# Ariel_v3.net
KiCad netlist of a schematic drawn in EAGLE
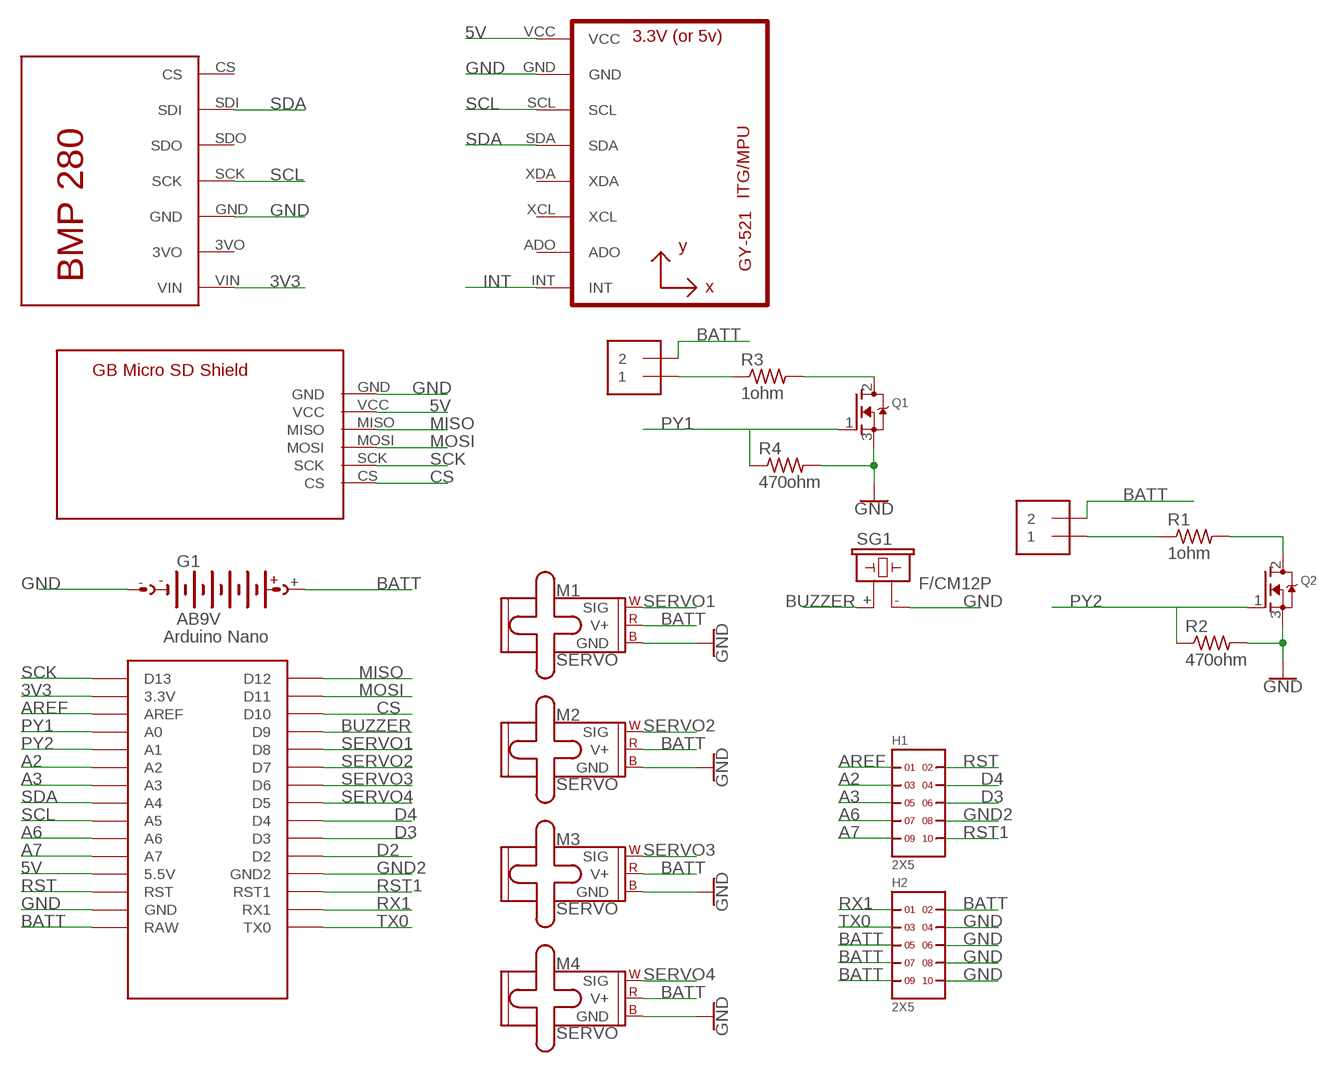
[diagram p0: schematic, sheet 1]

(export (version "E")
  (design (tool "Eeschema 10.0.6"))
  (components
    (comp (ref "G1")
      (value "AB9V")
      (footprint "eagle-import:AB9V")
      (libsource (lib "eagle-import") (part "AB9V"))
    )
    (comp (ref "H1")
      (value "2X5")
      (footprint "eagle-import:2X5")
      (libsource (lib "eagle-import") (part "2X5"))
    )
    (comp (ref "H2")
      (value "2X5")
      (footprint "eagle-import:2X5")
      (libsource (lib "eagle-import") (part "2X5"))
    )
    (comp (ref "J1")
      (value "1X2-3.5MM")
      (footprint "eagle-import:1X2-3.5MM")
      (libsource (lib "eagle-import") (part "1X2-3.5MM"))
    )
    (comp (ref "J2")
      (value "1X2-3.5MM")
      (footprint "eagle-import:1X2-3.5MM")
      (libsource (lib "eagle-import") (part "1X2-3.5MM"))
    )
    (comp (ref "M1")
      (value "SERVO")
      (footprint "eagle-import:1X03")
      (libsource (lib "eagle-import") (part "SERVO"))
    )
    (comp (ref "M2")
      (value "SERVO")
      (footprint "eagle-import:1X03")
      (libsource (lib "eagle-import") (part "SERVO"))
    )
    (comp (ref "M3")
      (value "SERVO")
      (footprint "eagle-import:1X03")
      (libsource (lib "eagle-import") (part "SERVO"))
    )
    (comp (ref "M4")
      (value "SERVO")
      (footprint "eagle-import:1X03")
      (libsource (lib "eagle-import") (part "SERVO"))
    )
    (comp (ref "Q1")
      (value "MOSFET-NGDS_TO220V")
      (footprint "eagle-import:TO220V")
      (libsource (lib "eagle-import") (part "MOSFET-NGDS_TO220V"))
    )
    (comp (ref "Q2")
      (value "MOSFET-NGDS_TO220V")
      (footprint "eagle-import:TO220V")
      (libsource (lib "eagle-import") (part "MOSFET-NGDS_TO220V"))
    )
    (comp (ref "R1")
      (value "1ohm")
      (footprint "eagle-import:0805-THM")
      (libsource (lib "eagle-import") (part "FLIPFLOP-RES"))
    )
    (comp (ref "R2")
      (value "470ohm")
      (footprint "eagle-import:0805-THM")
      (libsource (lib "eagle-import") (part "FLIPFLOP-RES"))
    )
    (comp (ref "R3")
      (value "1ohm")
      (footprint "eagle-import:0805-THM")
      (libsource (lib "eagle-import") (part "FLIPFLOP-RES"))
    )
    (comp (ref "R4")
      (value "470ohm")
      (footprint "eagle-import:0805-THM")
      (libsource (lib "eagle-import") (part "FLIPFLOP-RES"))
    )
    (comp (ref "SG1")
      (value "F/CM12P")
      (footprint "eagle-import:F_CM12P")
      (libsource (lib "eagle-import") (part "F/CM12P"))
    )
    (comp (ref "U$1")
      (value "NANO")
      (footprint "eagle-import:NANO")
      (libsource (lib "eagle-import") (part "NANO"))
    )
    (comp (ref "U$2")
      (value "BMP280")
      (footprint "eagle-import:BMP280")
      (libsource (lib "eagle-import") (part "BMP280"))
    )
    (comp (ref "U$3")
      (value "GBMICROSDSHIELD")
      (footprint "eagle-import:GBMICROSDSHIELD")
      (libsource (lib "eagle-import") (part "GBMICROSDSHIELD"))
    )
    (comp (ref "U1")
      (value "GY-521MPU6050")
      (footprint "eagle-import:GY-521")
      (libsource (lib "eagle-import") (part "GY-521MPU6050"))
    )
  )
  (nets
    (net (code "1") (name "/3V3") (class "Default")
      (node (ref "U$1") (pin "3.3V") (pinfunction "3.3V_3.3V") (pintype "bidirectional"))
      (node (ref "U$2") (pin "VIN") (pinfunction "VIN_VIN") (pintype "bidirectional"))
    )
    (net (code "2") (name "/5V") (class "Default")
      (node (ref "U$1") (pin "5V") (pinfunction "5.5V_5V") (pintype "bidirectional"))
      (node (ref "U$3") (pin "VCC") (pinfunction "VCC_VCC") (pintype "bidirectional"))
      (node (ref "U1") (pin "VCC") (pinfunction "VCC_VCC") (pintype "bidirectional"))
    )
    (net (code "3") (name "/A2") (class "Default")
      (node (ref "H1") (pin "3") (pinfunction "3_3") (pintype "bidirectional"))
      (node (ref "U$1") (pin "A2") (pinfunction "A2_A2") (pintype "bidirectional"))
    )
    (net (code "4") (name "/A3") (class "Default")
      (node (ref "H1") (pin "5") (pinfunction "5_5") (pintype "bidirectional"))
      (node (ref "U$1") (pin "A3") (pinfunction "A3_A3") (pintype "bidirectional"))
    )
    (net (code "5") (name "/A6") (class "Default")
      (node (ref "H1") (pin "7") (pinfunction "7_7") (pintype "bidirectional"))
      (node (ref "U$1") (pin "A6") (pinfunction "A6_A6") (pintype "bidirectional"))
    )
    (net (code "6") (name "/A7") (class "Default")
      (node (ref "H1") (pin "9") (pinfunction "9_9") (pintype "bidirectional"))
      (node (ref "U$1") (pin "A7") (pinfunction "A7_A7") (pintype "bidirectional"))
    )
    (net (code "7") (name "/AREF") (class "Default")
      (node (ref "H1") (pin "1") (pinfunction "1_1") (pintype "bidirectional"))
      (node (ref "U$1") (pin "AREF") (pinfunction "AREF_AREF") (pintype "bidirectional"))
    )
    (net (code "8") (name "/BATT") (class "Default")
      (node (ref "G1") (pin "+") (pinfunction "+_+") (pintype "passive"))
      (node (ref "H2") (pin "2") (pinfunction "2_2") (pintype "bidirectional"))
      (node (ref "H2") (pin "5") (pinfunction "5_5") (pintype "bidirectional"))
      (node (ref "H2") (pin "7") (pinfunction "7_7") (pintype "bidirectional"))
      (node (ref "H2") (pin "9") (pinfunction "9_9") (pintype "bidirectional"))
      (node (ref "J1") (pin "2") (pinfunction "2_2") (pintype "passive"))
      (node (ref "J2") (pin "2") (pinfunction "2_2") (pintype "passive"))
      (node (ref "M1") (pin "2") (pinfunction "V+_2") (pintype "bidirectional"))
      (node (ref "M2") (pin "2") (pinfunction "V+_2") (pintype "bidirectional"))
      (node (ref "M3") (pin "2") (pinfunction "V+_2") (pintype "bidirectional"))
      (node (ref "M4") (pin "2") (pinfunction "V+_2") (pintype "bidirectional"))
      (node (ref "U$1") (pin "RAW") (pinfunction "RAW_RAW") (pintype "bidirectional"))
    )
    (net (code "9") (name "/BUZZER") (class "Default")
      (node (ref "SG1") (pin "+") (pinfunction "1_+") (pintype "passive"))
      (node (ref "U$1") (pin "D9") (pinfunction "D9_D9") (pintype "bidirectional"))
    )
    (net (code "10") (name "/CS") (class "Default")
      (node (ref "U$1") (pin "D10") (pinfunction "D10_D10") (pintype "bidirectional"))
      (node (ref "U$3") (pin "CS") (pinfunction "CS_CS") (pintype "bidirectional"))
    )
    (net (code "11") (name "/D2") (class "Default")
      (node (ref "U$1") (pin "D2") (pinfunction "D2_D2") (pintype "bidirectional"))
    )
    (net (code "12") (name "/D3") (class "Default")
      (node (ref "H1") (pin "6") (pinfunction "6_6") (pintype "bidirectional"))
      (node (ref "U$1") (pin "D3") (pinfunction "D3_D3") (pintype "bidirectional"))
    )
    (net (code "13") (name "/D4") (class "Default")
      (node (ref "H1") (pin "4") (pinfunction "4_4") (pintype "bidirectional"))
      (node (ref "U$1") (pin "D4") (pinfunction "D4_D4") (pintype "bidirectional"))
    )
    (net (code "14") (name "/GND2") (class "Default")
      (node (ref "H1") (pin "8") (pinfunction "8_8") (pintype "bidirectional"))
      (node (ref "U$1") (pin "GND1") (pinfunction "GND2_GND1") (pintype "bidirectional"))
    )
    (net (code "15") (name "/INT") (class "Default")
      (node (ref "U1") (pin "INT") (pinfunction "INT_INT") (pintype "bidirectional"))
    )
    (net (code "16") (name "/MISO") (class "Default")
      (node (ref "U$1") (pin "D12") (pinfunction "D12_D12") (pintype "bidirectional"))
      (node (ref "U$3") (pin "MISO") (pinfunction "MISO_MISO") (pintype "bidirectional"))
    )
    (net (code "17") (name "/MOSI") (class "Default")
      (node (ref "U$1") (pin "D11") (pinfunction "D11_D11") (pintype "bidirectional"))
      (node (ref "U$3") (pin "MOSI") (pinfunction "MOSI_MOSI") (pintype "bidirectional"))
    )
    (net (code "18") (name "/PY1") (class "Default")
      (node (ref "Q1") (pin "1") (pinfunction "G_1") (pintype "bidirectional"))
      (node (ref "R4") (pin "1") (pinfunction "1_1") (pintype "passive"))
      (node (ref "U$1") (pin "A0") (pinfunction "A0_A0") (pintype "bidirectional"))
    )
    (net (code "19") (name "/PY2") (class "Default")
      (node (ref "Q2") (pin "1") (pinfunction "G_1") (pintype "bidirectional"))
      (node (ref "R2") (pin "1") (pinfunction "1_1") (pintype "passive"))
      (node (ref "U$1") (pin "A1") (pinfunction "A1_A1") (pintype "bidirectional"))
    )
    (net (code "20") (name "/RST") (class "Default")
      (node (ref "H1") (pin "2") (pinfunction "2_2") (pintype "bidirectional"))
      (node (ref "U$1") (pin "RST") (pinfunction "RST_RST") (pintype "bidirectional"))
    )
    (net (code "21") (name "/RST1") (class "Default")
      (node (ref "H1") (pin "10") (pinfunction "10_10") (pintype "bidirectional"))
      (node (ref "U$1") (pin "RST1") (pinfunction "RST1_RST1") (pintype "bidirectional"))
    )
    (net (code "22") (name "/RX1") (class "Default")
      (node (ref "H2") (pin "1") (pinfunction "1_1") (pintype "bidirectional"))
      (node (ref "U$1") (pin "RX1") (pinfunction "RX1_RX1") (pintype "bidirectional"))
    )
    (net (code "23") (name "/SCK") (class "Default")
      (node (ref "U$1") (pin "D13") (pinfunction "D13_D13") (pintype "bidirectional"))
      (node (ref "U$3") (pin "SCK") (pinfunction "SCK_SCK") (pintype "bidirectional"))
    )
    (net (code "24") (name "/SCL") (class "Default")
      (node (ref "U$1") (pin "A5") (pinfunction "A5_A5") (pintype "bidirectional"))
      (node (ref "U$2") (pin "SCK") (pinfunction "SCK_SCK") (pintype "bidirectional"))
      (node (ref "U1") (pin "SCL") (pinfunction "SCL_SCL") (pintype "bidirectional"))
    )
    (net (code "25") (name "/SDA") (class "Default")
      (node (ref "U$1") (pin "A4") (pinfunction "A4_A4") (pintype "bidirectional"))
      (node (ref "U$2") (pin "SDI") (pinfunction "SDI_SDI") (pintype "bidirectional"))
      (node (ref "U1") (pin "SDA") (pinfunction "SDA_SDA") (pintype "bidirectional"))
    )
    (net (code "26") (name "/SERVO1") (class "Default")
      (node (ref "M1") (pin "1") (pinfunction "SIG_1") (pintype "bidirectional"))
      (node (ref "U$1") (pin "D8") (pinfunction "D8_D8") (pintype "bidirectional"))
    )
    (net (code "27") (name "/SERVO2") (class "Default")
      (node (ref "M2") (pin "1") (pinfunction "SIG_1") (pintype "bidirectional"))
      (node (ref "U$1") (pin "D7") (pinfunction "D7_D7") (pintype "bidirectional"))
    )
    (net (code "28") (name "/SERVO3") (class "Default")
      (node (ref "M3") (pin "1") (pinfunction "SIG_1") (pintype "bidirectional"))
      (node (ref "U$1") (pin "D6") (pinfunction "D6_D6") (pintype "bidirectional"))
    )
    (net (code "29") (name "/SERVO4") (class "Default")
      (node (ref "M4") (pin "1") (pinfunction "SIG_1") (pintype "bidirectional"))
      (node (ref "U$1") (pin "D5") (pinfunction "D5_D5") (pintype "bidirectional"))
    )
    (net (code "30") (name "/TX0") (class "Default")
      (node (ref "H2") (pin "3") (pinfunction "3_3") (pintype "bidirectional"))
      (node (ref "U$1") (pin "TX0") (pinfunction "TX0_TX0") (pintype "bidirectional"))
    )
    (net (code "31") (name "GND") (class "Default")
      (node (ref "G1") (pin "-") (pinfunction "-_-") (pintype "passive"))
      (node (ref "H2") (pin "10") (pinfunction "10_10") (pintype "bidirectional"))
      (node (ref "H2") (pin "4") (pinfunction "4_4") (pintype "bidirectional"))
      (node (ref "H2") (pin "6") (pinfunction "6_6") (pintype "bidirectional"))
      (node (ref "H2") (pin "8") (pinfunction "8_8") (pintype "bidirectional"))
      (node (ref "M1") (pin "3") (pinfunction "GND_3") (pintype "bidirectional"))
      (node (ref "M2") (pin "3") (pinfunction "GND_3") (pintype "bidirectional"))
      (node (ref "M3") (pin "3") (pinfunction "GND_3") (pintype "bidirectional"))
      (node (ref "M4") (pin "3") (pinfunction "GND_3") (pintype "bidirectional"))
      (node (ref "Q1") (pin "3") (pinfunction "S_3") (pintype "bidirectional"))
      (node (ref "Q2") (pin "3") (pinfunction "S_3") (pintype "bidirectional"))
      (node (ref "R2") (pin "2") (pinfunction "2_2") (pintype "passive"))
      (node (ref "R4") (pin "2") (pinfunction "2_2") (pintype "passive"))
      (node (ref "SG1") (pin "-") (pinfunction "2_-") (pintype "passive"))
      (node (ref "U$1") (pin "GND") (pinfunction "GND_GND") (pintype "bidirectional"))
      (node (ref "U$2") (pin "GND") (pinfunction "GND_GND") (pintype "bidirectional"))
      (node (ref "U$3") (pin "GND") (pinfunction "GND_GND") (pintype "bidirectional"))
      (node (ref "U1") (pin "GND") (pinfunction "GND_GND") (pintype "bidirectional"))
    )
    (net (code "32") (name "Net-(J1-Pad1)") (class "Default")
      (node (ref "J1") (pin "1") (pinfunction "1_1") (pintype "passive"))
      (node (ref "R1") (pin "1") (pinfunction "1_1") (pintype "passive"))
    )
    (net (code "33") (name "Net-(J2-Pad1)") (class "Default")
      (node (ref "J2") (pin "1") (pinfunction "1_1") (pintype "passive"))
      (node (ref "R3") (pin "1") (pinfunction "1_1") (pintype "passive"))
    )
    (net (code "34") (name "Net-(Q1-D)") (class "Default")
      (node (ref "Q1") (pin "2") (pinfunction "D_2") (pintype "bidirectional"))
      (node (ref "R3") (pin "2") (pinfunction "2_2") (pintype "passive"))
    )
    (net (code "35") (name "Net-(Q2-D)") (class "Default")
      (node (ref "Q2") (pin "2") (pinfunction "D_2") (pintype "bidirectional"))
      (node (ref "R1") (pin "2") (pinfunction "2_2") (pintype "passive"))
    )
    (net (code "36") (name "unconnected-(U$1-PadICSP1)") (class "Default")
      (node (ref "U$1") (pin "ICSP1") (pinfunction "ICSP1_ICSP1") (pintype "bidirectional"))
    )
    (net (code "37") (name "unconnected-(U$1-PadICSP2)") (class "Default")
      (node (ref "U$1") (pin "ICSP2") (pinfunction "ICSP2_ICSP2") (pintype "bidirectional"))
    )
    (net (code "38") (name "unconnected-(U$1-PadICSP3)") (class "Default")
      (node (ref "U$1") (pin "ICSP3") (pinfunction "ICSP3_ICSP3") (pintype "bidirectional"))
    )
    (net (code "39") (name "unconnected-(U$1-PadICSP4)") (class "Default")
      (node (ref "U$1") (pin "ICSP4") (pinfunction "ICSP4_ICSP4") (pintype "bidirectional"))
    )
    (net (code "40") (name "unconnected-(U$1-PadICSP5)") (class "Default")
      (node (ref "U$1") (pin "ICSP5") (pinfunction "ICSP5_ICSP5") (pintype "bidirectional"))
    )
    (net (code "41") (name "unconnected-(U$1-PadICSP6)") (class "Default")
      (node (ref "U$1") (pin "ICSP6") (pinfunction "ICSP6_ICSP6") (pintype "bidirectional"))
    )
    (net (code "42") (name "unconnected-(U$2-Pad3VO)") (class "Default")
      (node (ref "U$2") (pin "3VO") (pinfunction "3VO_3VO") (pintype "bidirectional"))
    )
    (net (code "43") (name "unconnected-(U$2-PadCS)") (class "Default")
      (node (ref "U$2") (pin "CS") (pinfunction "CS_CS") (pintype "bidirectional"))
    )
    (net (code "44") (name "unconnected-(U$2-PadSDO)") (class "Default")
      (node (ref "U$2") (pin "SDO") (pinfunction "SDO_SDO") (pintype "bidirectional"))
    )
    (net (code "45") (name "unconnected-(U1-PadADO)") (class "Default")
      (node (ref "U1") (pin "ADO") (pinfunction "ADO_ADO") (pintype "bidirectional"))
    )
    (net (code "46") (name "unconnected-(U1-PadXCL)") (class "Default")
      (node (ref "U1") (pin "XCL") (pinfunction "XCL_XCL") (pintype "bidirectional"))
    )
    (net (code "47") (name "unconnected-(U1-PadXDA)") (class "Default")
      (node (ref "U1") (pin "XDA") (pinfunction "XDA_XDA") (pintype "bidirectional"))
    )
  )
)
